# Volant5_Push_button_v1_0.net
KiCad netlist of a schematic drawn in Altium Designer
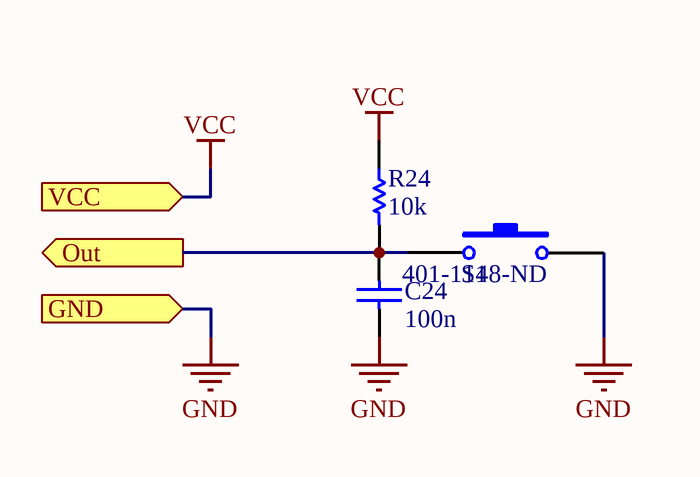
[diagram p0: Volant5.Push_button_v1.0.SchDoc]

(export (version "E")
  (design (tool "Eeschema 10.0.6"))
  (components
    (comp (ref "C24")
      (value "100n")
      (footprint "CS-0603")
      (fields
        (field (name "VOLTAGE") "16V")
        (field (name "TOLERANCE") "10%")
        (field (name "Comment") "CS - CAPACITOR")
      )
      (libsource (lib "CHINOOK_LIBRARY") (part "CS - CAPACITOR"))
    )
    (comp (ref "R24")
      (value "10k")
      (footprint "RS-0603")
      (fields
        (field (name "POWER") "RES POWER")
        (field (name "TOLERANCE") "RES TOL")
        (field (name "Comment") "RS - RESISTOR")
      )
      (libsource (lib "CHINOOK_LIBRARY") (part "RS - RESISTOR"))
    )
    (comp (ref "S1")
      (value "SW - Tactile Switch")
      (footprint "SW-ESE20C443")
      (fields (field (name "CAP BLACK") "401-1148-ND"))
      (libsource (lib "CHINOOK_LIBRARY") (part "SW - Tactile Switch"))
    )
  )
  (nets
    (net (code "1") (name "/Out") (class "Default")
      (node (ref "C24") (pin "2") (pinfunction "2_2") (pintype "passive"))
      (node (ref "R24") (pin "2") (pinfunction "2_2") (pintype "passive"))
      (node (ref "S1") (pin "1") (pinfunction "1_1") (pintype "passive"))
    )
    (net (code "2") (name "GND") (class "Default")
      (node (ref "C24") (pin "1") (pinfunction "1_1") (pintype "passive"))
      (node (ref "S1") (pin "2") (pinfunction "2_2") (pintype "passive"))
    )
    (net (code "3") (name "VCC") (class "Default")
      (node (ref "R24") (pin "1") (pinfunction "1_1") (pintype "passive"))
    )
  )
)
